# PixiFlood_1_10_PTH.net
KiCad netlist of a schematic drawn in EAGLE
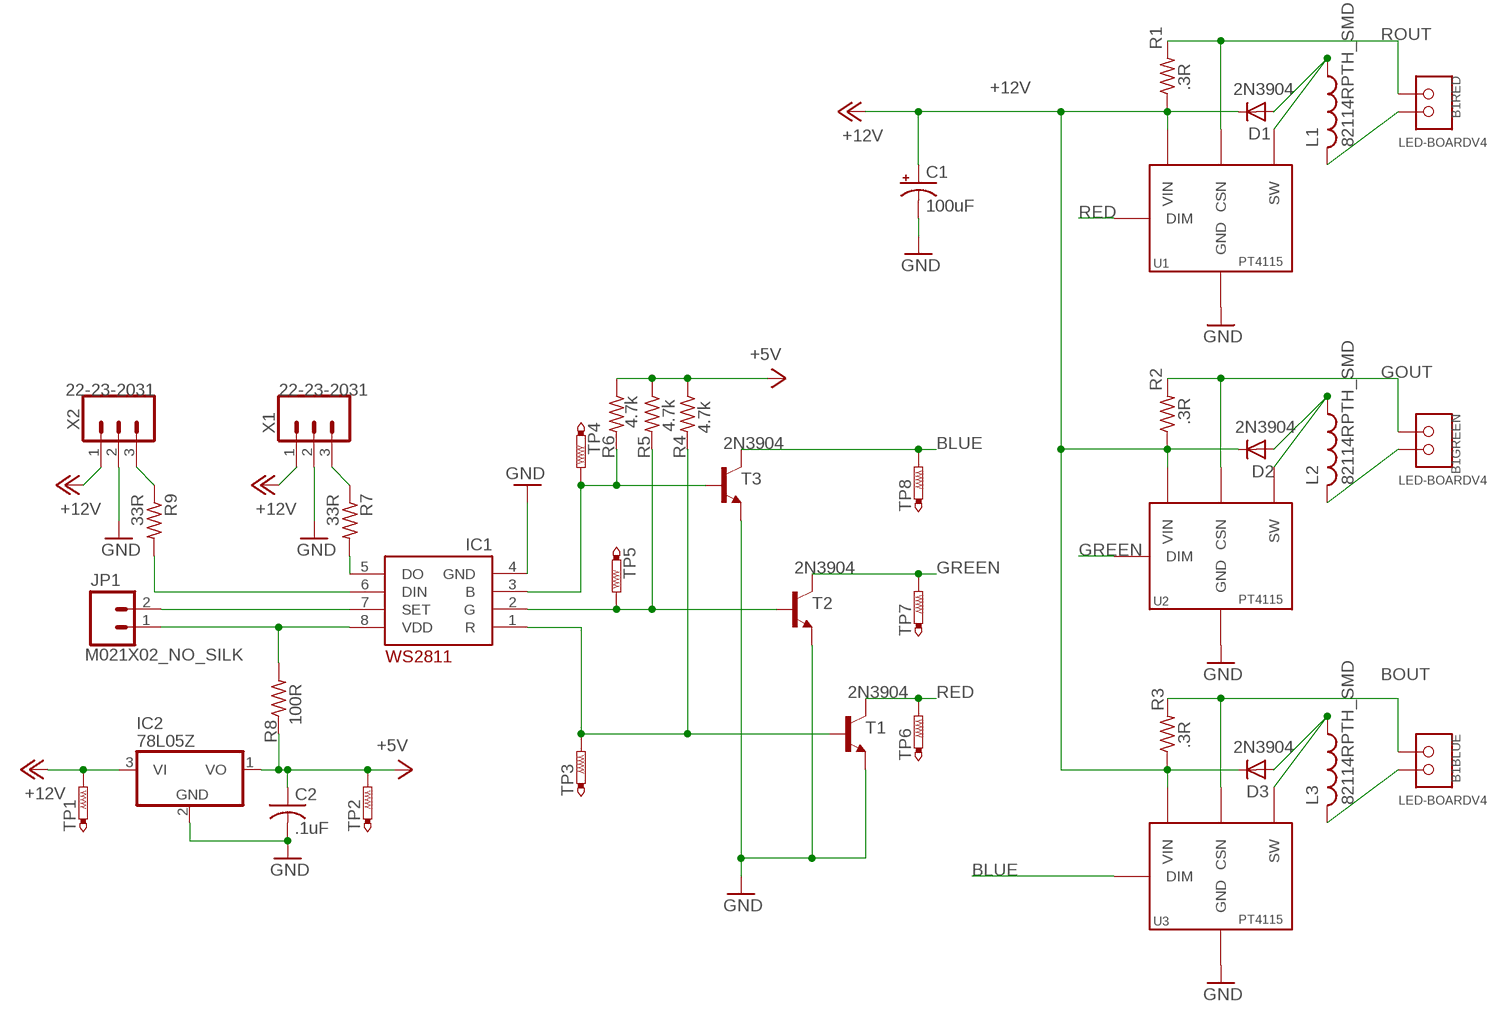
[diagram p0: schematic, sheet 1]

(export (version "E")
  (design (tool "Eeschema 10.0.6"))
  (components
    (comp (ref "B1")
      (value "LED-BOARDV4")
      (footprint "eagle-import:LED_BOARD-V4")
      (libsource (lib "eagle-import") (part "LED-BOARDV4"))
    )
    (comp (ref "C1")
      (value "100uF")
      (footprint "eagle-import:TT2D6L")
      (libsource (lib "eagle-import") (part "CPOL-USTT2D6L"))
    )
    (comp (ref "C2")
      (value ".1uF")
      (footprint "eagle-import:C050-024X044")
      (libsource (lib "eagle-import") (part "C-US050-024X044"))
    )
    (comp (ref "D1")
      (value "2N3904")
      (footprint "eagle-import:DO07")
      (libsource (lib "eagle-import") (part "DIODE-DO07"))
    )
    (comp (ref "D2")
      (value "2N3904")
      (footprint "eagle-import:DO07")
      (libsource (lib "eagle-import") (part "DIODE-DO07"))
    )
    (comp (ref "D3")
      (value "2N3904")
      (footprint "eagle-import:DO07")
      (libsource (lib "eagle-import") (part "DIODE-DO07"))
    )
    (comp (ref "IC1")
      (value "WS2811-SOP8")
      (footprint "eagle-import:SO08-SKINNYPADS")
      (libsource (lib "eagle-import") (part "WS2811-SOP8"))
    )
    (comp (ref "IC2")
      (value "78L05Z")
      (footprint "eagle-import:TO92")
      (libsource (lib "eagle-import") (part "78ZL05"))
    )
    (comp (ref "JP1")
      (value "M021X02_NO_SILK")
      (footprint "eagle-import:1X02_NO_SILK")
      (libsource (lib "eagle-import") (part "M021X02_NO_SILK"))
    )
    (comp (ref "L1")
      (value "82114RPTH_SMD")
      (footprint "eagle-import:INDUCTOR")
      (libsource (lib "eagle-import") (part "82114RPTH_SMD"))
    )
    (comp (ref "L2")
      (value "82114RPTH_SMD")
      (footprint "eagle-import:INDUCTOR")
      (libsource (lib "eagle-import") (part "82114RPTH_SMD"))
    )
    (comp (ref "L3")
      (value "82114RPTH_SMD")
      (footprint "eagle-import:INDUCTOR")
      (libsource (lib "eagle-import") (part "82114RPTH_SMD"))
    )
    (comp (ref "R1")
      (value ".3R")
      (footprint "eagle-import:0204_7")
      (libsource (lib "eagle-import") (part "resistor_R-US_0204/7"))
    )
    (comp (ref "R2")
      (value ".3R")
      (footprint "eagle-import:0204_7")
      (libsource (lib "eagle-import") (part "resistor_R-US_0204/7"))
    )
    (comp (ref "R3")
      (value ".3R")
      (footprint "eagle-import:0204_7")
      (libsource (lib "eagle-import") (part "resistor_R-US_0204/7"))
    )
    (comp (ref "R4")
      (value "4.7k")
      (footprint "eagle-import:0204_7")
      (libsource (lib "eagle-import") (part "resistor_R-US_0204/7"))
    )
    (comp (ref "R5")
      (value "4.7k")
      (footprint "eagle-import:0204_7")
      (libsource (lib "eagle-import") (part "resistor_R-US_0204/7"))
    )
    (comp (ref "R6")
      (value "4.7k")
      (footprint "eagle-import:0204_7")
      (libsource (lib "eagle-import") (part "resistor_R-US_0204/7"))
    )
    (comp (ref "R7")
      (value "33R")
      (footprint "eagle-import:0204_7")
      (libsource (lib "eagle-import") (part "R-US_0204/7"))
    )
    (comp (ref "R8")
      (value "100R")
      (footprint "eagle-import:0204_7")
      (libsource (lib "eagle-import") (part "R-US_0204/7"))
    )
    (comp (ref "R9")
      (value "33R")
      (footprint "eagle-import:0204_7")
      (libsource (lib "eagle-import") (part "R-US_0204/7"))
    )
    (comp (ref "T1")
      (value "2N3904")
      (footprint "eagle-import:TO92")
      (libsource (lib "eagle-import") (part "2N3904"))
    )
    (comp (ref "T2")
      (value "2N3904")
      (footprint "eagle-import:TO92")
      (libsource (lib "eagle-import") (part "2N3904"))
    )
    (comp (ref "T3")
      (value "2N3904")
      (footprint "eagle-import:TO92")
      (libsource (lib "eagle-import") (part "2N3904"))
    )
    (comp (ref "TP1")
      (value "PTR1B2,54")
      (footprint "eagle-import:B2,54")
      (libsource (lib "eagle-import") (part "PTR1B2,54"))
    )
    (comp (ref "TP2")
      (value "PTR1B2,54")
      (footprint "eagle-import:B2,54")
      (libsource (lib "eagle-import") (part "PTR1B2,54"))
    )
    (comp (ref "TP3")
      (value "PTR1B1,27")
      (footprint "eagle-import:B1,27")
      (libsource (lib "eagle-import") (part "PTR1B1,27"))
    )
    (comp (ref "TP4")
      (value "PTR1B1,27")
      (footprint "eagle-import:B1,27")
      (libsource (lib "eagle-import") (part "PTR1B1,27"))
    )
    (comp (ref "TP5")
      (value "PTR1B1,27")
      (footprint "eagle-import:B1,27")
      (libsource (lib "eagle-import") (part "PTR1B1,27"))
    )
    (comp (ref "TP6")
      (value "PTR1B1,27")
      (footprint "eagle-import:B1,27")
      (libsource (lib "eagle-import") (part "PTR1B1,27"))
    )
    (comp (ref "TP7")
      (value "PTR1B1,27")
      (footprint "eagle-import:B1,27")
      (libsource (lib "eagle-import") (part "PTR1B1,27"))
    )
    (comp (ref "TP8")
      (value "PTR1B1,27")
      (footprint "eagle-import:B1,27")
      (libsource (lib "eagle-import") (part "PTR1B1,27"))
    )
    (comp (ref "U1")
      (value "PT4115B89E-A2")
      (footprint "eagle-import:SOT89-5-A")
      (libsource (lib "eagle-import") (part "PT4115B89E-A2"))
    )
    (comp (ref "U2")
      (value "PT4115B89E-A2")
      (footprint "eagle-import:SOT89-5-A")
      (libsource (lib "eagle-import") (part "PT4115B89E-A2"))
    )
    (comp (ref "U3")
      (value "PT4115B89E-A2")
      (footprint "eagle-import:SOT89-5-A")
      (libsource (lib "eagle-import") (part "PT4115B89E-A2"))
    )
    (comp (ref "X1")
      (value "22-23-2031")
      (footprint "eagle-import:22-23-2031")
      (fields (field (name "MF") "MOLEX"))
      (libsource (lib "eagle-import") (part "22-23-2031"))
    )
    (comp (ref "X2")
      (value "22-23-2031")
      (footprint "eagle-import:22-23-2031")
      (fields (field (name "MF") "MOLEX"))
      (libsource (lib "eagle-import") (part "22-23-2031"))
    )
  )
  (nets
    (net (code "1") (name "+5V") (class "Default")
      (node (ref "C2") (pin "1") (pinfunction "1_1") (pintype "passive"))
      (node (ref "IC2") (pin "1") (pinfunction "VO_1") (pintype "passive"))
      (node (ref "R4") (pin "1") (pinfunction "1_1") (pintype "passive"))
      (node (ref "R5") (pin "1") (pinfunction "1_1") (pintype "passive"))
      (node (ref "R6") (pin "1") (pinfunction "1_1") (pintype "passive"))
      (node (ref "R8") (pin "1") (pinfunction "1_1") (pintype "passive"))
      (node (ref "TP2") (pin "TP") (pinfunction "TP_TP") (pintype "input"))
    )
    (net (code "2") (name "+12V") (class "Default")
      (node (ref "C1") (pin "+") (pinfunction "+_+") (pintype "passive"))
      (node (ref "D1") (pin "C") (pinfunction "C_C") (pintype "passive"))
      (node (ref "D2") (pin "C") (pinfunction "C_C") (pintype "passive"))
      (node (ref "D3") (pin "C") (pinfunction "C_C") (pintype "passive"))
      (node (ref "IC2") (pin "3") (pinfunction "VI_3") (pintype "input"))
      (node (ref "R1") (pin "1") (pinfunction "1_1") (pintype "passive"))
      (node (ref "R2") (pin "1") (pinfunction "1_1") (pintype "passive"))
      (node (ref "R3") (pin "1") (pinfunction "1_1") (pintype "passive"))
      (node (ref "TP1") (pin "TP") (pinfunction "TP_TP") (pintype "input"))
      (node (ref "U1") (pin "5") (pinfunction "VIN_5") (pintype "power_in"))
      (node (ref "U2") (pin "5") (pinfunction "VIN_5") (pintype "power_in"))
      (node (ref "U3") (pin "5") (pinfunction "VIN_5") (pintype "power_in"))
      (node (ref "X1") (pin "1") (pinfunction "1_1") (pintype "passive"))
      (node (ref "X2") (pin "1") (pinfunction "1_1") (pintype "passive"))
    )
    (net (code "3") (name "/BLUE") (class "Default")
      (node (ref "T3") (pin "1") (pinfunction "C_1") (pintype "passive"))
      (node (ref "TP8") (pin "TP") (pinfunction "TP_TP") (pintype "input"))
      (node (ref "U3") (pin "3") (pinfunction "DIM_3") (pintype "bidirectional"))
    )
    (net (code "4") (name "/BOUT") (class "Default")
      (node (ref "B1") (pin "B+") (pinfunction "P$2_B+") (pintype "bidirectional"))
      (node (ref "B1") (pin "B+@2") (pinfunction "P$2_B+@2") (pintype "bidirectional"))
      (node (ref "R3") (pin "2") (pinfunction "2_2") (pintype "passive"))
      (node (ref "U3") (pin "4") (pinfunction "CSN_4") (pintype "bidirectional"))
    )
    (net (code "5") (name "/GOUT") (class "Default")
      (node (ref "B1") (pin "G+") (pinfunction "P$2_G+") (pintype "bidirectional"))
      (node (ref "B1") (pin "G+@1") (pinfunction "P$2_G+@1") (pintype "bidirectional"))
      (node (ref "R2") (pin "2") (pinfunction "2_2") (pintype "passive"))
      (node (ref "U2") (pin "4") (pinfunction "CSN_4") (pintype "bidirectional"))
    )
    (net (code "6") (name "/GREEN") (class "Default")
      (node (ref "T2") (pin "1") (pinfunction "C_1") (pintype "passive"))
      (node (ref "TP7") (pin "TP") (pinfunction "TP_TP") (pintype "input"))
      (node (ref "U2") (pin "3") (pinfunction "DIM_3") (pintype "bidirectional"))
    )
    (net (code "7") (name "/RED") (class "Default")
      (node (ref "T1") (pin "1") (pinfunction "C_1") (pintype "passive"))
      (node (ref "TP6") (pin "TP") (pinfunction "TP_TP") (pintype "input"))
      (node (ref "U1") (pin "3") (pinfunction "DIM_3") (pintype "bidirectional"))
    )
    (net (code "8") (name "/ROUT") (class "Default")
      (node (ref "B1") (pin "R+") (pinfunction "P$2_R+") (pintype "bidirectional"))
      (node (ref "B1") (pin "R+@1") (pinfunction "P$2_R+@1") (pintype "bidirectional"))
      (node (ref "R1") (pin "2") (pinfunction "2_2") (pintype "passive"))
      (node (ref "U1") (pin "4") (pinfunction "CSN_4") (pintype "bidirectional"))
    )
    (net (code "9") (name "GND") (class "Default")
      (node (ref "C1") (pin "-") (pinfunction "-_-") (pintype "passive"))
      (node (ref "C2") (pin "2") (pinfunction "2_2") (pintype "passive"))
      (node (ref "IC1") (pin "4") (pinfunction "GND_4") (pintype "power_in"))
      (node (ref "IC2") (pin "2") (pinfunction "GND_2") (pintype "passive"))
      (node (ref "T1") (pin "3") (pinfunction "E_3") (pintype "passive"))
      (node (ref "T2") (pin "3") (pinfunction "E_3") (pintype "passive"))
      (node (ref "T3") (pin "3") (pinfunction "E_3") (pintype "passive"))
      (node (ref "U1") (pin "2") (pinfunction "GND_2") (pintype "power_in"))
      (node (ref "U1") (pin "2@1") (pinfunction "GND_2@1") (pintype "power_in"))
      (node (ref "U1") (pin "2@2") (pinfunction "GND_2@2") (pintype "power_in"))
      (node (ref "U1") (pin "2@3") (pinfunction "GND_2@3") (pintype "power_in"))
      (node (ref "U2") (pin "2") (pinfunction "GND_2") (pintype "power_in"))
      (node (ref "U2") (pin "2@1") (pinfunction "GND_2@1") (pintype "power_in"))
      (node (ref "U2") (pin "2@2") (pinfunction "GND_2@2") (pintype "power_in"))
      (node (ref "U2") (pin "2@3") (pinfunction "GND_2@3") (pintype "power_in"))
      (node (ref "U3") (pin "2") (pinfunction "GND_2") (pintype "power_in"))
      (node (ref "U3") (pin "2@1") (pinfunction "GND_2@1") (pintype "power_in"))
      (node (ref "U3") (pin "2@2") (pinfunction "GND_2@2") (pintype "power_in"))
      (node (ref "U3") (pin "2@3") (pinfunction "GND_2@3") (pintype "power_in"))
      (node (ref "X1") (pin "2") (pinfunction "2_2") (pintype "passive"))
      (node (ref "X2") (pin "2") (pinfunction "2_2") (pintype "passive"))
    )
    (net (code "10") (name "Net-(B1A-P$1-PadB-)") (class "Default")
      (node (ref "B1") (pin "B-") (pinfunction "P$1_B-") (pintype "bidirectional"))
      (node (ref "B1") (pin "B-@1") (pinfunction "P$1_B-@1") (pintype "bidirectional"))
      (node (ref "L3") (pin "2") (pinfunction "2_2") (pintype "passive"))
      (node (ref "L3") (pin "2@A") (pinfunction "2_2@A") (pintype "passive"))
    )
    (net (code "11") (name "Net-(B1B-P$1-PadG-)") (class "Default")
      (node (ref "B1") (pin "G-") (pinfunction "P$1_G-") (pintype "bidirectional"))
      (node (ref "B1") (pin "G-@1") (pinfunction "P$1_G-@1") (pintype "bidirectional"))
      (node (ref "L2") (pin "2") (pinfunction "2_2") (pintype "passive"))
      (node (ref "L2") (pin "2@A") (pinfunction "2_2@A") (pintype "passive"))
    )
    (net (code "12") (name "Net-(B1C-P$1-PadR-)") (class "Default")
      (node (ref "B1") (pin "R-") (pinfunction "P$1_R-") (pintype "bidirectional"))
      (node (ref "B1") (pin "R-@1") (pinfunction "P$1_R-@1") (pintype "bidirectional"))
      (node (ref "L1") (pin "2") (pinfunction "2_2") (pintype "passive"))
      (node (ref "L1") (pin "2@A") (pinfunction "2_2@A") (pintype "passive"))
    )
    (net (code "13") (name "Net-(IC1-B)") (class "Default")
      (node (ref "IC1") (pin "3") (pinfunction "B_3") (pintype "open_collector"))
      (node (ref "R6") (pin "2") (pinfunction "2_2") (pintype "passive"))
      (node (ref "T3") (pin "2") (pinfunction "B_2") (pintype "passive"))
      (node (ref "TP4") (pin "TP") (pinfunction "TP_TP") (pintype "input"))
    )
    (net (code "14") (name "Net-(IC1-DIN)") (class "Default")
      (node (ref "IC1") (pin "6") (pinfunction "DIN_6") (pintype "input"))
      (node (ref "R9") (pin "2") (pinfunction "2_2") (pintype "passive"))
    )
    (net (code "15") (name "Net-(IC1-DO)") (class "Default")
      (node (ref "IC1") (pin "5") (pinfunction "DO_5") (pintype "output"))
      (node (ref "R7") (pin "2") (pinfunction "2_2") (pintype "passive"))
    )
    (net (code "16") (name "Net-(IC1-G)") (class "Default")
      (node (ref "IC1") (pin "2") (pinfunction "G_2") (pintype "open_collector"))
      (node (ref "R5") (pin "2") (pinfunction "2_2") (pintype "passive"))
      (node (ref "T2") (pin "2") (pinfunction "B_2") (pintype "passive"))
      (node (ref "TP5") (pin "TP") (pinfunction "TP_TP") (pintype "input"))
    )
    (net (code "17") (name "Net-(IC1-R)") (class "Default")
      (node (ref "IC1") (pin "1") (pinfunction "R_1") (pintype "open_collector"))
      (node (ref "R4") (pin "2") (pinfunction "2_2") (pintype "passive"))
      (node (ref "T1") (pin "2") (pinfunction "B_2") (pintype "passive"))
      (node (ref "TP3") (pin "TP") (pinfunction "TP_TP") (pintype "input"))
    )
    (net (code "18") (name "Net-(IC1-SET)") (class "Default")
      (node (ref "IC1") (pin "7") (pinfunction "SET_7") (pintype "input"))
      (node (ref "JP1") (pin "2") (pinfunction "2_2") (pintype "passive"))
    )
    (net (code "19") (name "Net-(IC1-VDD)") (class "Default")
      (node (ref "IC1") (pin "8") (pinfunction "VDD_8") (pintype "power_in"))
      (node (ref "JP1") (pin "1") (pinfunction "1_1") (pintype "passive"))
      (node (ref "R8") (pin "2") (pinfunction "2_2") (pintype "passive"))
    )
    (net (code "20") (name "Net-(R7-Pad1)") (class "Default")
      (node (ref "R7") (pin "1") (pinfunction "1_1") (pintype "passive"))
      (node (ref "X1") (pin "3") (pinfunction "3_3") (pintype "passive"))
    )
    (net (code "21") (name "Net-(R9-Pad1)") (class "Default")
      (node (ref "R9") (pin "1") (pinfunction "1_1") (pintype "passive"))
      (node (ref "X2") (pin "3") (pinfunction "3_3") (pintype "passive"))
    )
    (net (code "22") (name "Net-(U1-SW)") (class "Default")
      (node (ref "D1") (pin "A") (pinfunction "A_A") (pintype "passive"))
      (node (ref "L1") (pin "1") (pinfunction "1_1") (pintype "passive"))
      (node (ref "L1") (pin "1@A") (pinfunction "1_1@A") (pintype "passive"))
      (node (ref "U1") (pin "1") (pinfunction "SW_1") (pintype "bidirectional"))
    )
    (net (code "23") (name "Net-(U2-SW)") (class "Default")
      (node (ref "D2") (pin "A") (pinfunction "A_A") (pintype "passive"))
      (node (ref "L2") (pin "1") (pinfunction "1_1") (pintype "passive"))
      (node (ref "L2") (pin "1@A") (pinfunction "1_1@A") (pintype "passive"))
      (node (ref "U2") (pin "1") (pinfunction "SW_1") (pintype "bidirectional"))
    )
    (net (code "24") (name "Net-(U3-SW)") (class "Default")
      (node (ref "D3") (pin "A") (pinfunction "A_A") (pintype "passive"))
      (node (ref "L3") (pin "1") (pinfunction "1_1") (pintype "passive"))
      (node (ref "L3") (pin "1@A") (pinfunction "1_1@A") (pintype "passive"))
      (node (ref "U3") (pin "1") (pinfunction "SW_1") (pintype "bidirectional"))
    )
  )
)
